# dropper_torpedo.net
KiCad netlist of a schematic drawn in EAGLE
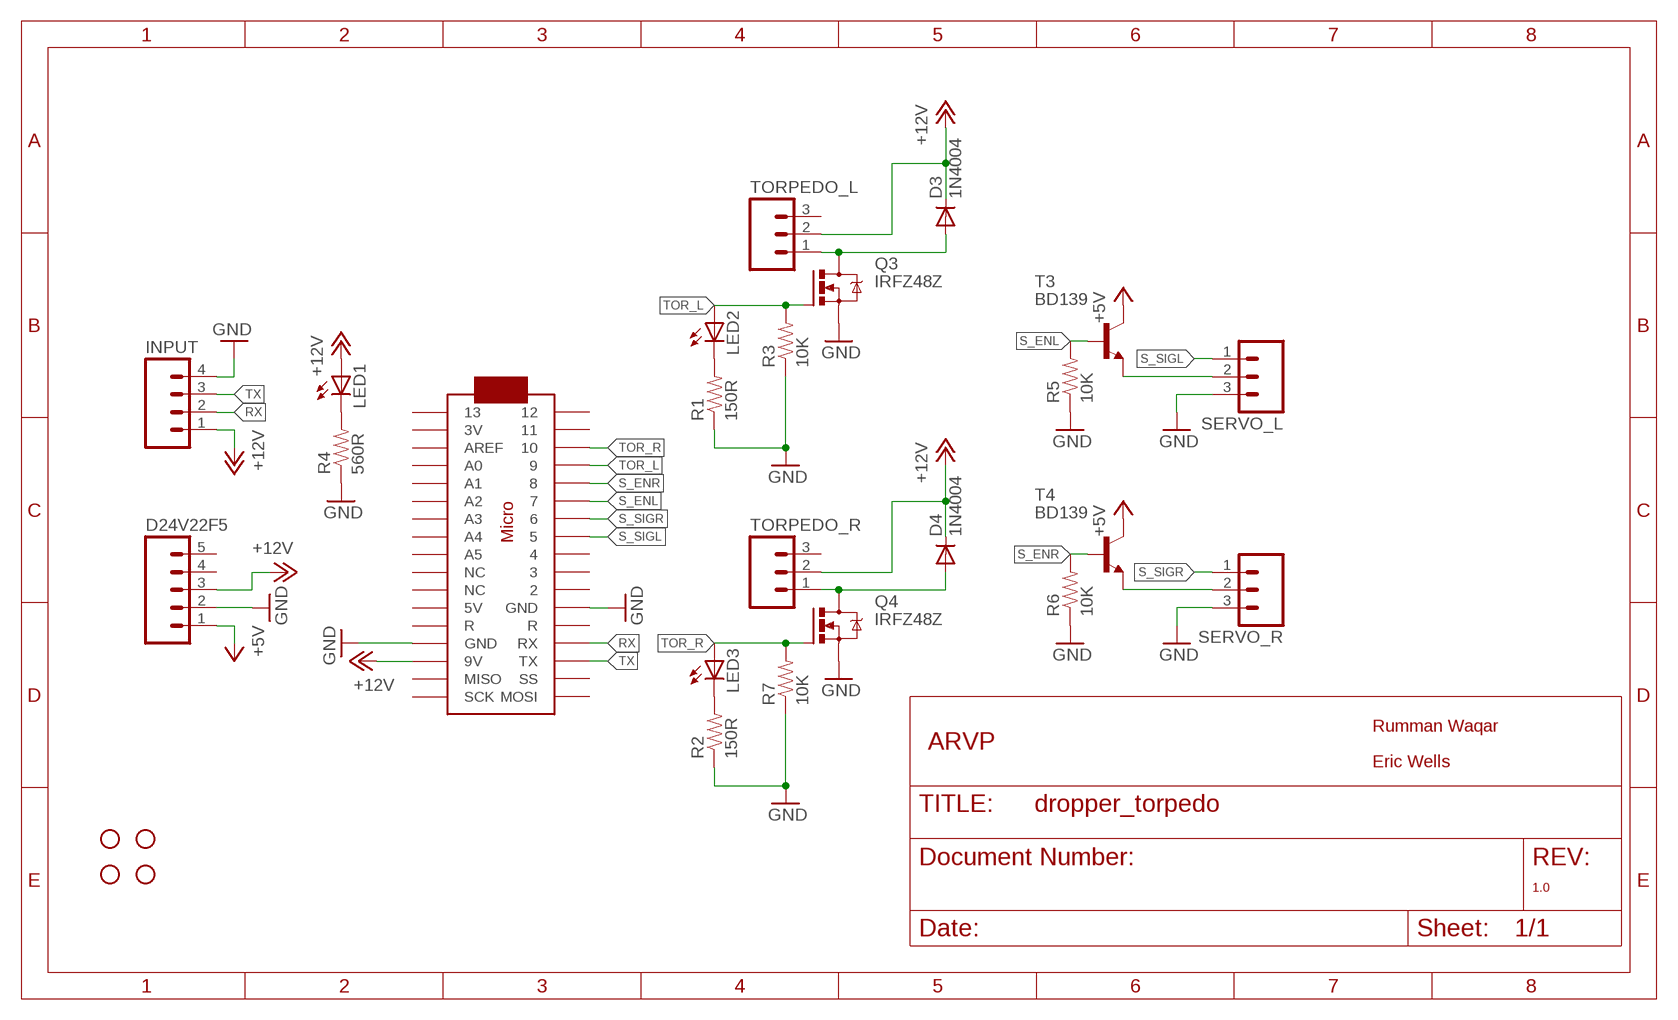
[diagram p0: schematic, sheet 1]

(export (version "E")
  (design (tool "Eeschema 10.0.6"))
  (components
    (comp (ref "D3")
      (value "1N4004")
      (footprint "eagle-import:DO41-10")
      (libsource (lib "eagle-import") (part "1N4004"))
    )
    (comp (ref "D4")
      (value "1N4004")
      (footprint "eagle-import:DO41-10")
      (libsource (lib "eagle-import") (part "1N4004"))
    )
    (comp (ref "D24V22F5")
      (value "M05PTH")
      (footprint "eagle-import:1X05")
      (libsource (lib "eagle-import") (part "M05PTH"))
    )
    (comp (ref "INPUT")
      (value "M04POLAR")
      (footprint "eagle-import:MOLEX-1X4")
      (libsource (lib "eagle-import") (part "M04POLAR"))
    )
    (comp (ref "JP1")
      (value "STAND-OFF")
      (footprint "eagle-import:STAND-OFF")
      (libsource (lib "eagle-import") (part "STAND-OFF"))
    )
    (comp (ref "JP2")
      (value "STAND-OFF")
      (footprint "eagle-import:STAND-OFF")
      (libsource (lib "eagle-import") (part "STAND-OFF"))
    )
    (comp (ref "JP3")
      (value "STAND-OFF")
      (footprint "eagle-import:STAND-OFF")
      (libsource (lib "eagle-import") (part "STAND-OFF"))
    )
    (comp (ref "JP4")
      (value "STAND-OFF")
      (footprint "eagle-import:STAND-OFF")
      (libsource (lib "eagle-import") (part "STAND-OFF"))
    )
    (comp (ref "LED1")
      (value "LED0603")
      (footprint "eagle-import:LED-0603")
      (libsource (lib "eagle-import") (part "LED0603"))
    )
    (comp (ref "LED2")
      (value "LED0603")
      (footprint "eagle-import:LED-0603")
      (libsource (lib "eagle-import") (part "LED0603"))
    )
    (comp (ref "LED3")
      (value "LED0603")
      (footprint "eagle-import:LED-0603")
      (libsource (lib "eagle-import") (part "LED0603"))
    )
    (comp (ref "Q3")
      (value "IRFZ48Z")
      (footprint "eagle-import:TO220BH")
      (libsource (lib "eagle-import") (part "IRFZ48Z"))
    )
    (comp (ref "Q4")
      (value "IRFZ48Z")
      (footprint "eagle-import:TO220BH")
      (libsource (lib "eagle-import") (part "IRFZ48Z"))
    )
    (comp (ref "R1")
      (value "150R")
      (footprint "eagle-import:0805")
      (libsource (lib "eagle-import") (part "RESISTOR0805-RES"))
    )
    (comp (ref "R2")
      (value "150R")
      (footprint "eagle-import:0805")
      (libsource (lib "eagle-import") (part "RESISTOR0805-RES"))
    )
    (comp (ref "R3")
      (value "10K")
      (footprint "eagle-import:0805")
      (libsource (lib "eagle-import") (part "RESISTOR0805-RES"))
    )
    (comp (ref "R4")
      (value "560R")
      (footprint "eagle-import:0805")
      (libsource (lib "eagle-import") (part "RESISTOR0805-RES"))
    )
    (comp (ref "R5")
      (value "10K")
      (footprint "eagle-import:0805")
      (libsource (lib "eagle-import") (part "RESISTOR0805-RES"))
    )
    (comp (ref "R6")
      (value "10K")
      (footprint "eagle-import:0805")
      (libsource (lib "eagle-import") (part "RESISTOR0805-RES"))
    )
    (comp (ref "R7")
      (value "10K")
      (footprint "eagle-import:0805")
      (libsource (lib "eagle-import") (part "RESISTOR0805-RES"))
    )
    (comp (ref "SERVO_L")
      (value "M03POLAR")
      (footprint "eagle-import:MOLEX-1X3")
      (libsource (lib "eagle-import") (part "M03POLAR"))
    )
    (comp (ref "SERVO_R")
      (value "M03POLAR")
      (footprint "eagle-import:MOLEX-1X3")
      (libsource (lib "eagle-import") (part "M03POLAR"))
    )
    (comp (ref "T3")
      (value "BD139")
      (footprint "eagle-import:TO126")
      (libsource (lib "eagle-import") (part "BD139"))
    )
    (comp (ref "T4")
      (value "BD139")
      (footprint "eagle-import:TO126")
      (libsource (lib "eagle-import") (part "BD139"))
    )
    (comp (ref "TORPEDO_L")
      (value "M03POLAR")
      (footprint "eagle-import:MOLEX-1X3")
      (libsource (lib "eagle-import") (part "M03POLAR"))
    )
    (comp (ref "TORPEDO_R")
      (value "M03POLAR")
      (footprint "eagle-import:MOLEX-1X3")
      (libsource (lib "eagle-import") (part "M03POLAR"))
    )
    (comp (ref "U$1")
      (value "ARVP_LOGO")
      (footprint "eagle-import:ARVP")
      (libsource (lib "eagle-import") (part "ARVP_LOGO"))
    )
    (comp (ref "U$2")
      (value "ARDUINOMICRO")
      (footprint "eagle-import:ARDUINOMICRO")
      (libsource (lib "eagle-import") (part "ARDUINOMICRO"))
    )
  )
  (nets
    (net (code "1") (name "+5V") (class "Default")
      (node (ref "D24V22F5") (pin "1") (pinfunction "1_1") (pintype "passive"))
      (node (ref "T3") (pin "2") (pinfunction "C_2") (pintype "passive"))
      (node (ref "T4") (pin "2") (pinfunction "C_2") (pintype "passive"))
    )
    (net (code "2") (name "+12V") (class "Default")
      (node (ref "D24V22F5") (pin "3") (pinfunction "3_3") (pintype "passive"))
      (node (ref "D3") (pin "C") (pinfunction "C_C") (pintype "passive"))
      (node (ref "D4") (pin "C") (pinfunction "C_C") (pintype "passive"))
      (node (ref "INPUT") (pin "1") (pinfunction "1_1") (pintype "passive"))
      (node (ref "LED1") (pin "A") (pinfunction "A_A") (pintype "passive"))
      (node (ref "TORPEDO_L") (pin "2") (pinfunction "2_2") (pintype "passive"))
      (node (ref "TORPEDO_R") (pin "2") (pinfunction "2_2") (pintype "passive"))
      (node (ref "U$2") (pin "P$20") (pinfunction "9V_P$20") (pintype "bidirectional"))
    )
    (net (code "3") (name "GND") (class "Default")
      (node (ref "D24V22F5") (pin "2") (pinfunction "2_2") (pintype "passive"))
      (node (ref "INPUT") (pin "4") (pinfunction "4_4") (pintype "passive"))
      (node (ref "Q3") (pin "S") (pinfunction "S_S") (pintype "passive"))
      (node (ref "Q4") (pin "S") (pinfunction "S_S") (pintype "passive"))
      (node (ref "R1") (pin "1") (pinfunction "1_1") (pintype "passive"))
      (node (ref "R2") (pin "1") (pinfunction "1_1") (pintype "passive"))
      (node (ref "R3") (pin "1") (pinfunction "1_1") (pintype "passive"))
      (node (ref "R4") (pin "1") (pinfunction "1_1") (pintype "passive"))
      (node (ref "R5") (pin "1") (pinfunction "1_1") (pintype "passive"))
      (node (ref "R6") (pin "1") (pinfunction "1_1") (pintype "passive"))
      (node (ref "R7") (pin "1") (pinfunction "1_1") (pintype "passive"))
      (node (ref "SERVO_L") (pin "3") (pinfunction "3_3") (pintype "passive"))
      (node (ref "SERVO_R") (pin "3") (pinfunction "3_3") (pintype "passive"))
      (node (ref "U$2") (pin "P$12") (pinfunction "GND_P$12") (pintype "bidirectional"))
      (node (ref "U$2") (pin "P$21") (pinfunction "GND_P$21") (pintype "bidirectional"))
    )
    (net (code "4") (name "Net-(D3-PadA)") (class "Default")
      (node (ref "D3") (pin "A") (pinfunction "A_A") (pintype "passive"))
      (node (ref "Q3") (pin "D") (pinfunction "D_D") (pintype "passive"))
      (node (ref "TORPEDO_L") (pin "1") (pinfunction "1_1") (pintype "passive"))
    )
    (net (code "5") (name "Net-(D4-PadA)") (class "Default")
      (node (ref "D4") (pin "A") (pinfunction "A_A") (pintype "passive"))
      (node (ref "Q4") (pin "D") (pinfunction "D_D") (pintype "passive"))
      (node (ref "TORPEDO_R") (pin "1") (pinfunction "1_1") (pintype "passive"))
    )
    (net (code "6") (name "Net-(LED1-PadC)") (class "Default")
      (node (ref "LED1") (pin "C") (pinfunction "C_C") (pintype "passive"))
      (node (ref "R4") (pin "2") (pinfunction "2_2") (pintype "passive"))
    )
    (net (code "7") (name "Net-(LED2-PadC)") (class "Default")
      (node (ref "LED2") (pin "C") (pinfunction "C_C") (pintype "passive"))
      (node (ref "R1") (pin "2") (pinfunction "2_2") (pintype "passive"))
    )
    (net (code "8") (name "Net-(LED3-PadC)") (class "Default")
      (node (ref "LED3") (pin "C") (pinfunction "C_C") (pintype "passive"))
      (node (ref "R2") (pin "2") (pinfunction "2_2") (pintype "passive"))
    )
    (net (code "9") (name "Net-(T3-E)") (class "Default")
      (node (ref "SERVO_L") (pin "2") (pinfunction "2_2") (pintype "passive"))
      (node (ref "T3") (pin "1") (pinfunction "E_1") (pintype "passive"))
    )
    (net (code "10") (name "Net-(T4-E)") (class "Default")
      (node (ref "SERVO_R") (pin "2") (pinfunction "2_2") (pintype "passive"))
      (node (ref "T4") (pin "1") (pinfunction "E_1") (pintype "passive"))
    )
    (net (code "11") (name "RX") (class "Default")
      (node (ref "INPUT") (pin "2") (pinfunction "2_2") (pintype "passive"))
      (node (ref "U$2") (pin "P$14") (pinfunction "RX_P$14") (pintype "bidirectional"))
    )
    (net (code "12") (name "S_ENL") (class "Default")
      (node (ref "R5") (pin "2") (pinfunction "2_2") (pintype "passive"))
      (node (ref "T3") (pin "3") (pinfunction "B_3") (pintype "passive"))
      (node (ref "U$2") (pin "P$6") (pinfunction "7_P$6") (pintype "bidirectional"))
    )
    (net (code "13") (name "S_ENR") (class "Default")
      (node (ref "R6") (pin "2") (pinfunction "2_2") (pintype "passive"))
      (node (ref "T4") (pin "3") (pinfunction "B_3") (pintype "passive"))
      (node (ref "U$2") (pin "P$5") (pinfunction "8_P$5") (pintype "bidirectional"))
    )
    (net (code "14") (name "S_SIGL") (class "Default")
      (node (ref "SERVO_L") (pin "1") (pinfunction "1_1") (pintype "passive"))
      (node (ref "U$2") (pin "P$8") (pinfunction "5_P$8") (pintype "bidirectional"))
    )
    (net (code "15") (name "S_SIGR") (class "Default")
      (node (ref "SERVO_R") (pin "1") (pinfunction "1_1") (pintype "passive"))
      (node (ref "U$2") (pin "P$7") (pinfunction "6_P$7") (pintype "bidirectional"))
    )
    (net (code "16") (name "TOR_L") (class "Default")
      (node (ref "LED2") (pin "A") (pinfunction "A_A") (pintype "passive"))
      (node (ref "Q3") (pin "G") (pinfunction "G_G") (pintype "passive"))
      (node (ref "R3") (pin "2") (pinfunction "2_2") (pintype "passive"))
      (node (ref "U$2") (pin "P$4") (pinfunction "9_P$4") (pintype "bidirectional"))
    )
    (net (code "17") (name "TOR_R") (class "Default")
      (node (ref "LED3") (pin "A") (pinfunction "A_A") (pintype "passive"))
      (node (ref "Q4") (pin "G") (pinfunction "G_G") (pintype "passive"))
      (node (ref "R7") (pin "2") (pinfunction "2_2") (pintype "passive"))
      (node (ref "U$2") (pin "P$3") (pinfunction "10_P$3") (pintype "bidirectional"))
    )
    (net (code "18") (name "TX") (class "Default")
      (node (ref "INPUT") (pin "3") (pinfunction "3_3") (pintype "passive"))
      (node (ref "U$2") (pin "P$15") (pinfunction "TX_P$15") (pintype "bidirectional"))
    )
    (net (code "19") (name "unconnected-(D24V22F5-Pad4)") (class "Default")
      (node (ref "D24V22F5") (pin "4") (pinfunction "4_4") (pintype "passive"))
    )
    (net (code "20") (name "unconnected-(D24V22F5-Pad5)") (class "Default")
      (node (ref "D24V22F5") (pin "5") (pinfunction "5_5") (pintype "passive"))
    )
    (net (code "21") (name "unconnected-(TORPEDO_L-Pad3)") (class "Default")
      (node (ref "TORPEDO_L") (pin "3") (pinfunction "3_3") (pintype "passive"))
    )
    (net (code "22") (name "unconnected-(TORPEDO_R-Pad3)") (class "Default")
      (node (ref "TORPEDO_R") (pin "3") (pinfunction "3_3") (pintype "passive"))
    )
    (net (code "23") (name "unconnected-(U$2-2-PadP$11)") (class "Default")
      (node (ref "U$2") (pin "P$11") (pinfunction "2_P$11") (pintype "bidirectional"))
    )
    (net (code "24") (name "unconnected-(U$2-3-PadP$10)") (class "Default")
      (node (ref "U$2") (pin "P$10") (pinfunction "3_P$10") (pintype "bidirectional"))
    )
    (net (code "25") (name "unconnected-(U$2-3V-PadP$33)") (class "Default")
      (node (ref "U$2") (pin "P$33") (pinfunction "3V_P$33") (pintype "bidirectional"))
    )
    (net (code "26") (name "unconnected-(U$2-4-PadP$9)") (class "Default")
      (node (ref "U$2") (pin "P$9") (pinfunction "4_P$9") (pintype "bidirectional"))
    )
    (net (code "27") (name "unconnected-(U$2-5V-PadP$23)") (class "Default")
      (node (ref "U$2") (pin "P$23") (pinfunction "5V_P$23") (pintype "bidirectional"))
    )
    (net (code "28") (name "unconnected-(U$2-11-PadP$2)") (class "Default")
      (node (ref "U$2") (pin "P$2") (pinfunction "11_P$2") (pintype "bidirectional"))
    )
    (net (code "29") (name "unconnected-(U$2-12-PadP$1)") (class "Default")
      (node (ref "U$2") (pin "P$1") (pinfunction "12_P$1") (pintype "bidirectional"))
    )
    (net (code "30") (name "unconnected-(U$2-13-PadP$34)") (class "Default")
      (node (ref "U$2") (pin "P$34") (pinfunction "13_P$34") (pintype "bidirectional"))
    )
    (net (code "31") (name "unconnected-(U$2-A0-PadP$31)") (class "Default")
      (node (ref "U$2") (pin "P$31") (pinfunction "A0_P$31") (pintype "bidirectional"))
    )
    (net (code "32") (name "unconnected-(U$2-A1-PadP$30)") (class "Default")
      (node (ref "U$2") (pin "P$30") (pinfunction "A1_P$30") (pintype "bidirectional"))
    )
    (net (code "33") (name "unconnected-(U$2-A2-PadP$29)") (class "Default")
      (node (ref "U$2") (pin "P$29") (pinfunction "A2_P$29") (pintype "bidirectional"))
    )
    (net (code "34") (name "unconnected-(U$2-A3-PadP$28)") (class "Default")
      (node (ref "U$2") (pin "P$28") (pinfunction "A3_P$28") (pintype "bidirectional"))
    )
    (net (code "35") (name "unconnected-(U$2-A4-PadP$27)") (class "Default")
      (node (ref "U$2") (pin "P$27") (pinfunction "A4_P$27") (pintype "bidirectional"))
    )
    (net (code "36") (name "unconnected-(U$2-A5-PadP$26)") (class "Default")
      (node (ref "U$2") (pin "P$26") (pinfunction "A5_P$26") (pintype "bidirectional"))
    )
    (net (code "37") (name "unconnected-(U$2-AREF-PadP$32)") (class "Default")
      (node (ref "U$2") (pin "P$32") (pinfunction "AREF_P$32") (pintype "bidirectional"))
    )
    (net (code "38") (name "unconnected-(U$2-MISO-PadP$19)") (class "Default")
      (node (ref "U$2") (pin "P$19") (pinfunction "MISO_P$19") (pintype "bidirectional"))
    )
    (net (code "39") (name "unconnected-(U$2-MOSI-PadP$17)") (class "Default")
      (node (ref "U$2") (pin "P$17") (pinfunction "MOSI_P$17") (pintype "bidirectional"))
    )
    (net (code "40") (name "unconnected-(U$2-NC-PadP$24)") (class "Default")
      (node (ref "U$2") (pin "P$24") (pinfunction "NC_P$24") (pintype "bidirectional"))
    )
    (net (code "41") (name "unconnected-(U$2-NC-PadP$25)") (class "Default")
      (node (ref "U$2") (pin "P$25") (pinfunction "NC_P$25") (pintype "bidirectional"))
    )
    (net (code "42") (name "unconnected-(U$2-R-PadP$13)") (class "Default")
      (node (ref "U$2") (pin "P$13") (pinfunction "R_P$13") (pintype "bidirectional"))
    )
    (net (code "43") (name "unconnected-(U$2-R-PadP$22)") (class "Default")
      (node (ref "U$2") (pin "P$22") (pinfunction "R_P$22") (pintype "bidirectional"))
    )
    (net (code "44") (name "unconnected-(U$2-SCK-PadP$18)") (class "Default")
      (node (ref "U$2") (pin "P$18") (pinfunction "SCK_P$18") (pintype "bidirectional"))
    )
    (net (code "45") (name "unconnected-(U$2-SS-PadP$16)") (class "Default")
      (node (ref "U$2") (pin "P$16") (pinfunction "SS_P$16") (pintype "bidirectional"))
    )
  )
)
